# working.net
KiCad netlist of a schematic drawn in EAGLE
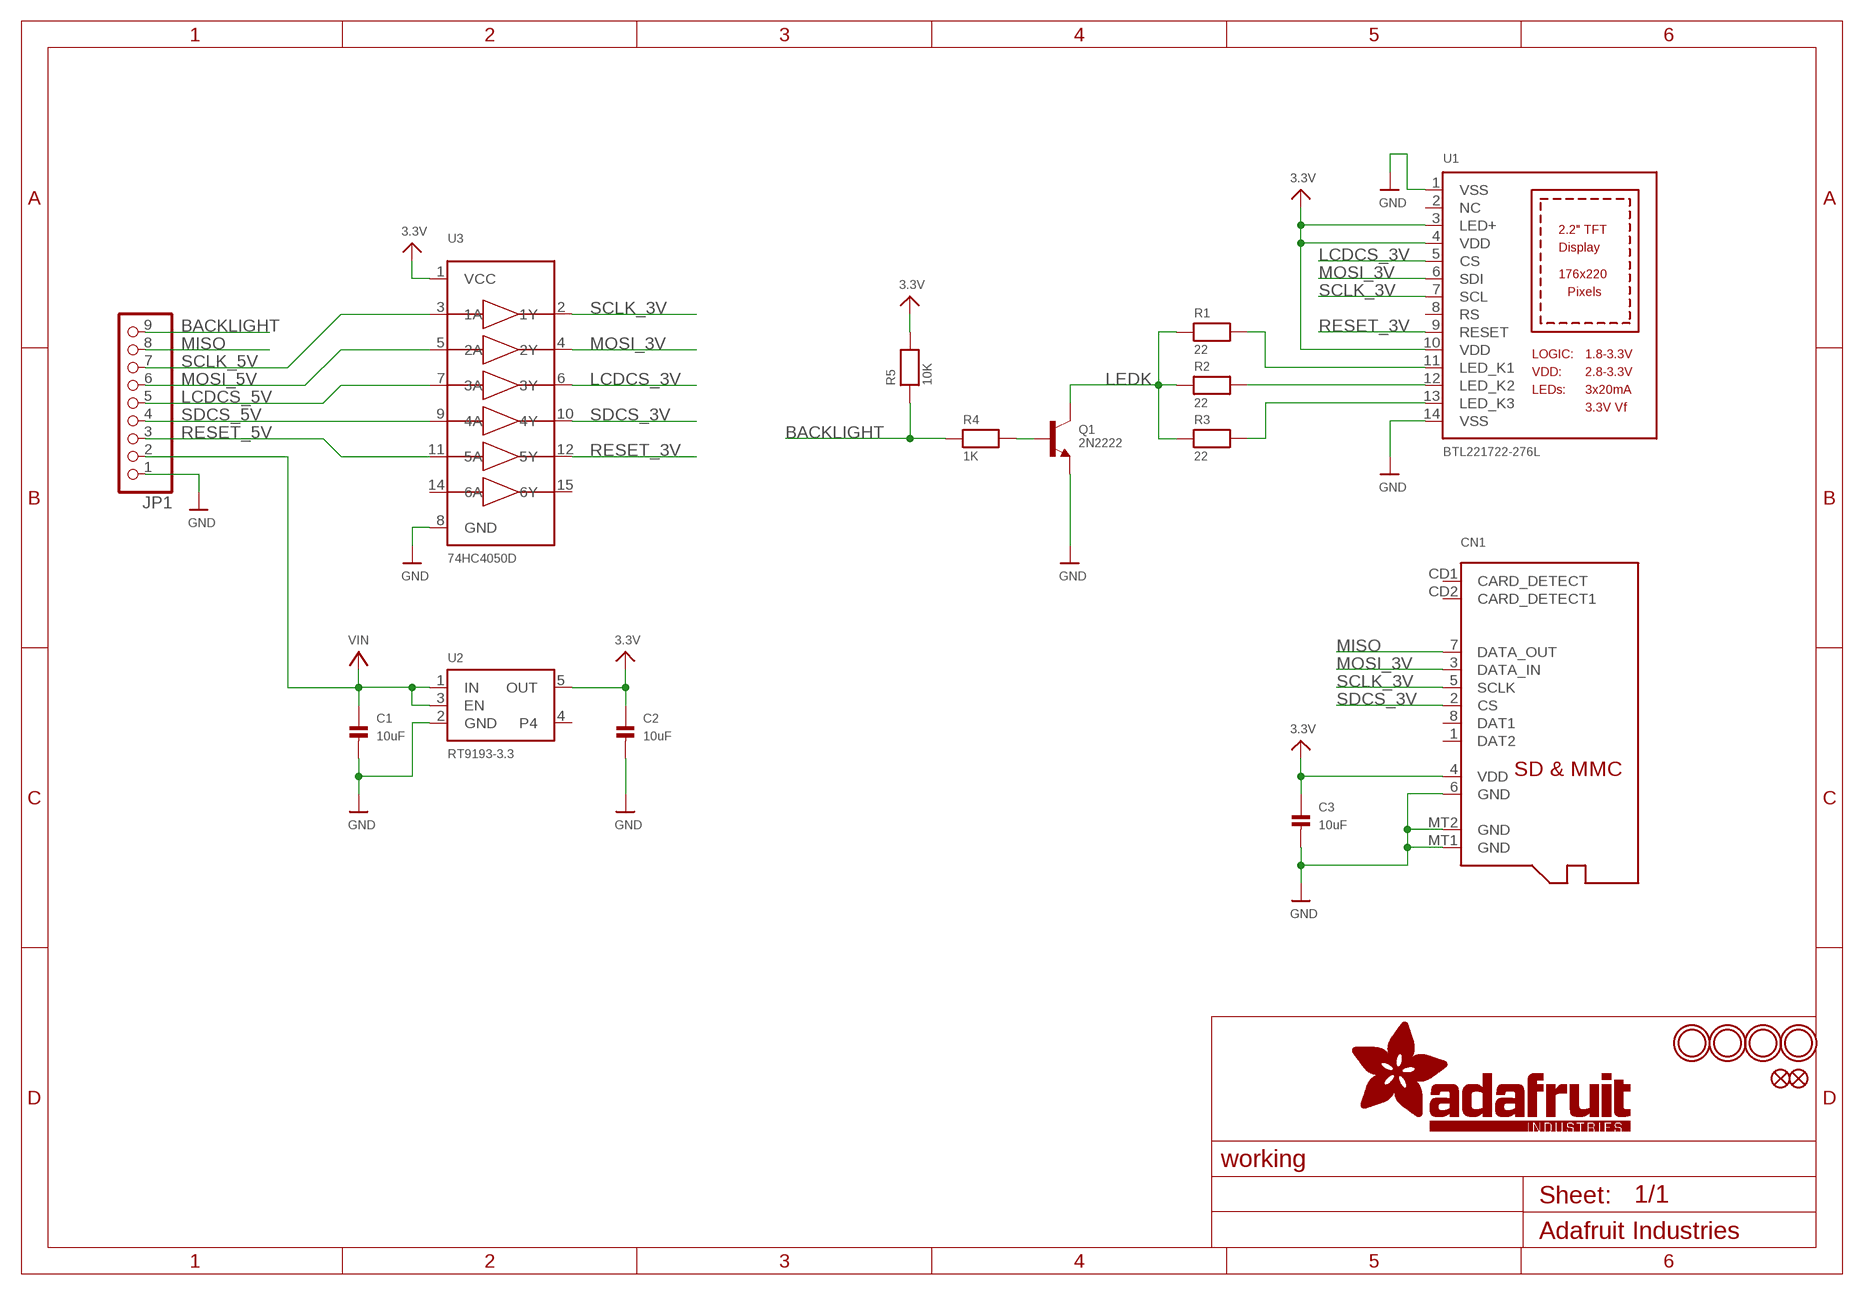
[diagram p0: schematic, sheet 1]

(export (version "E")
  (design (tool "Eeschema 10.0.6"))
  (components
    (comp (ref "C1")
      (value "10uF")
      (footprint "eagle-import:0805")
      (libsource (lib "eagle-import") (part "CAP_CERAMIC0805"))
    )
    (comp (ref "C2")
      (value "10uF")
      (footprint "eagle-import:0805")
      (libsource (lib "eagle-import") (part "CAP_CERAMIC0805"))
    )
    (comp (ref "C3")
      (value "10uF")
      (footprint "eagle-import:0805")
      (libsource (lib "eagle-import") (part "CAP_CERAMIC0805"))
    )
    (comp (ref "CN1")
      (value "MICROSD")
      (footprint "eagle-import:MICROSD")
      (libsource (lib "eagle-import") (part "MICROSD"))
    )
    (comp (ref "FID1")
      (value "FIDUCIAL\"\"")
      (footprint "eagle-import:FIDUCIAL_1MM")
      (libsource (lib "eagle-import") (part "FIDUCIAL{dblquote}{dblquote}"))
    )
    (comp (ref "FID2")
      (value "FIDUCIAL\"\"")
      (footprint "eagle-import:FIDUCIAL_1MM")
      (libsource (lib "eagle-import") (part "FIDUCIAL{dblquote}{dblquote}"))
    )
    (comp (ref "JP1")
      (value "HEADER-1X970MIL")
      (footprint "eagle-import:1X09_ROUND_70")
      (libsource (lib "eagle-import") (part "HEADER-1X970MIL"))
    )
    (comp (ref "Q1")
      (value "2N2222")
      (footprint "eagle-import:SOT23-WIDE")
      (libsource (lib "eagle-import") (part "TRANSISTOR_NPNWIDE"))
    )
    (comp (ref "R1")
      (value "22")
      (footprint "eagle-import:0805")
      (libsource (lib "eagle-import") (part "RESISTOR0805"))
    )
    (comp (ref "R2")
      (value "22")
      (footprint "eagle-import:0805")
      (libsource (lib "eagle-import") (part "RESISTOR0805"))
    )
    (comp (ref "R3")
      (value "22")
      (footprint "eagle-import:0805")
      (libsource (lib "eagle-import") (part "RESISTOR0805"))
    )
    (comp (ref "R4")
      (value "1K")
      (footprint "eagle-import:0805")
      (libsource (lib "eagle-import") (part "RESISTOR0805"))
    )
    (comp (ref "R5")
      (value "10K")
      (footprint "eagle-import:0805")
      (libsource (lib "eagle-import") (part "RESISTOR0805"))
    )
    (comp (ref "U$2")
      (value "MOUNTINGHOLE2.5")
      (footprint "eagle-import:MOUNTINGHOLE_2.5_PLATED")
      (libsource (lib "eagle-import") (part "MOUNTINGHOLE2.5"))
    )
    (comp (ref "U$3")
      (value "MOUNTINGHOLE2.5")
      (footprint "eagle-import:MOUNTINGHOLE_2.5_PLATED")
      (libsource (lib "eagle-import") (part "MOUNTINGHOLE2.5"))
    )
    (comp (ref "U$4")
      (value "MOUNTINGHOLE2.5")
      (footprint "eagle-import:MOUNTINGHOLE_2.5_PLATED")
      (libsource (lib "eagle-import") (part "MOUNTINGHOLE2.5"))
    )
    (comp (ref "U$5")
      (value "MOUNTINGHOLE2.5")
      (footprint "eagle-import:MOUNTINGHOLE_2.5_PLATED")
      (libsource (lib "eagle-import") (part "MOUNTINGHOLE2.5"))
    )
    (comp (ref "U1")
      (value "BTL221722-276L")
      (footprint "eagle-import:BTL221722-276L")
      (libsource (lib "eagle-import") (part "DISP_LCD_BTL221722-276L"))
    )
    (comp (ref "U2")
      (value "RT9193-3.3")
      (footprint "eagle-import:SOT23-5")
      (libsource (lib "eagle-import") (part "VREG_SOT23-5"))
    )
    (comp (ref "U3")
      (value "74HC4050D")
      (footprint "eagle-import:SOIC16")
      (libsource (lib "eagle-import") (part "74HC4050D"))
    )
  )
  (nets
    (net (code "1") (name "/BACKLIGHT") (class "Default")
      (node (ref "JP1") (pin "9") (pinfunction "9_9") (pintype "passive"))
      (node (ref "R4") (pin "1") (pinfunction "1_1") (pintype "passive"))
      (node (ref "R5") (pin "1") (pinfunction "1_1") (pintype "passive"))
    )
    (net (code "2") (name "/LCDCS_3V") (class "Default")
      (node (ref "U1") (pin "5") (pinfunction "CS_5") (pintype "bidirectional"))
      (node (ref "U3") (pin "6") (pinfunction "3Y_6") (pintype "bidirectional"))
    )
    (net (code "3") (name "/LCDCS_5V") (class "Default")
      (node (ref "JP1") (pin "5") (pinfunction "5_5") (pintype "passive"))
      (node (ref "U3") (pin "7") (pinfunction "3A_7") (pintype "bidirectional"))
    )
    (net (code "4") (name "/LEDK") (class "Default")
      (node (ref "Q1") (pin "3") (pinfunction "C_3") (pintype "passive"))
      (node (ref "R1") (pin "1") (pinfunction "1_1") (pintype "passive"))
      (node (ref "R2") (pin "1") (pinfunction "1_1") (pintype "passive"))
      (node (ref "R3") (pin "1") (pinfunction "1_1") (pintype "passive"))
    )
    (net (code "5") (name "/MISO") (class "Default")
      (node (ref "CN1") (pin "7") (pinfunction "DATA_OUT_7") (pintype "output"))
      (node (ref "JP1") (pin "8") (pinfunction "8_8") (pintype "passive"))
    )
    (net (code "6") (name "/MOSI_3V") (class "Default")
      (node (ref "CN1") (pin "3") (pinfunction "DATA_IN_3") (pintype "input"))
      (node (ref "U1") (pin "6") (pinfunction "SDI_6") (pintype "bidirectional"))
      (node (ref "U3") (pin "4") (pinfunction "2Y_4") (pintype "bidirectional"))
    )
    (net (code "7") (name "/MOSI_5V") (class "Default")
      (node (ref "JP1") (pin "6") (pinfunction "6_6") (pintype "passive"))
      (node (ref "U3") (pin "5") (pinfunction "2A_5") (pintype "bidirectional"))
    )
    (net (code "8") (name "/RESET_3V") (class "Default")
      (node (ref "U1") (pin "9") (pinfunction "RESET_9") (pintype "bidirectional"))
      (node (ref "U3") (pin "12") (pinfunction "5Y_12") (pintype "bidirectional"))
    )
    (net (code "9") (name "/RESET_5V") (class "Default")
      (node (ref "JP1") (pin "3") (pinfunction "3_3") (pintype "passive"))
      (node (ref "U3") (pin "11") (pinfunction "5A_11") (pintype "bidirectional"))
    )
    (net (code "10") (name "/SCLK_3V") (class "Default")
      (node (ref "CN1") (pin "5") (pinfunction "SCLK_5") (pintype "input"))
      (node (ref "U1") (pin "7") (pinfunction "SCL_7") (pintype "bidirectional"))
      (node (ref "U3") (pin "2") (pinfunction "1Y_2") (pintype "bidirectional"))
    )
    (net (code "11") (name "/SCLK_5V") (class "Default")
      (node (ref "JP1") (pin "7") (pinfunction "7_7") (pintype "passive"))
      (node (ref "U3") (pin "3") (pinfunction "1A_3") (pintype "bidirectional"))
    )
    (net (code "12") (name "/SDCS_3V") (class "Default")
      (node (ref "CN1") (pin "2") (pinfunction "CS_2") (pintype "input"))
      (node (ref "U3") (pin "10") (pinfunction "4Y_10") (pintype "bidirectional"))
    )
    (net (code "13") (name "/SDCS_5V") (class "Default")
      (node (ref "JP1") (pin "4") (pinfunction "4_4") (pintype "passive"))
      (node (ref "U3") (pin "9") (pinfunction "4A_9") (pintype "bidirectional"))
    )
    (net (code "14") (name "3.3V") (class "Default")
      (node (ref "C2") (pin "1") (pinfunction "P$1_1") (pintype "passive"))
      (node (ref "C3") (pin "1") (pinfunction "P$1_1") (pintype "passive"))
      (node (ref "CN1") (pin "4") (pinfunction "VDD_4") (pintype "power_in"))
      (node (ref "R5") (pin "2") (pinfunction "2_2") (pintype "passive"))
      (node (ref "U1") (pin "10") (pinfunction "VDD_10") (pintype "power_in"))
      (node (ref "U1") (pin "3") (pinfunction "LED+_3") (pintype "power_in"))
      (node (ref "U1") (pin "4") (pinfunction "VDD_4") (pintype "power_in"))
      (node (ref "U2") (pin "5") (pinfunction "OUT_5") (pintype "bidirectional"))
      (node (ref "U3") (pin "1") (pinfunction "VCC_1") (pintype "bidirectional"))
    )
    (net (code "15") (name "GND") (class "Default")
      (node (ref "C1") (pin "2") (pinfunction "P$2_2") (pintype "passive"))
      (node (ref "C2") (pin "2") (pinfunction "P$2_2") (pintype "passive"))
      (node (ref "C3") (pin "2") (pinfunction "P$2_2") (pintype "passive"))
      (node (ref "CN1") (pin "6") (pinfunction "GND_6") (pintype "power_in"))
      (node (ref "CN1") (pin "MT1") (pinfunction "GND_MT1") (pintype "power_in"))
      (node (ref "CN1") (pin "MT2") (pinfunction "GND_MT2") (pintype "power_in"))
      (node (ref "JP1") (pin "1") (pinfunction "1_1") (pintype "passive"))
      (node (ref "Q1") (pin "2") (pinfunction "E_2") (pintype "passive"))
      (node (ref "U1") (pin "1") (pinfunction "VSS_1") (pintype "power_in"))
      (node (ref "U1") (pin "14") (pinfunction "VSS_14") (pintype "power_in"))
      (node (ref "U2") (pin "2") (pinfunction "GND_2") (pintype "bidirectional"))
      (node (ref "U3") (pin "8") (pinfunction "GND_8") (pintype "bidirectional"))
    )
    (net (code "16") (name "Net-(Q1-B)") (class "Default")
      (node (ref "Q1") (pin "1") (pinfunction "B_1") (pintype "passive"))
      (node (ref "R4") (pin "2") (pinfunction "2_2") (pintype "passive"))
    )
    (net (code "17") (name "Net-(U1-LED_K1)") (class "Default")
      (node (ref "R1") (pin "2") (pinfunction "2_2") (pintype "passive"))
      (node (ref "U1") (pin "11") (pinfunction "LED_K1_11") (pintype "power_in"))
    )
    (net (code "18") (name "Net-(U1-LED_K2)") (class "Default")
      (node (ref "R2") (pin "2") (pinfunction "2_2") (pintype "passive"))
      (node (ref "U1") (pin "12") (pinfunction "LED_K2_12") (pintype "power_in"))
    )
    (net (code "19") (name "Net-(U1-LED_K3)") (class "Default")
      (node (ref "R3") (pin "2") (pinfunction "2_2") (pintype "passive"))
      (node (ref "U1") (pin "13") (pinfunction "LED_K3_13") (pintype "power_in"))
    )
    (net (code "20") (name "VIN") (class "Default")
      (node (ref "C1") (pin "1") (pinfunction "P$1_1") (pintype "passive"))
      (node (ref "JP1") (pin "2") (pinfunction "2_2") (pintype "passive"))
      (node (ref "U2") (pin "1") (pinfunction "IN_1") (pintype "bidirectional"))
      (node (ref "U2") (pin "3") (pinfunction "EN_3") (pintype "bidirectional"))
    )
    (net (code "21") (name "unconnected-(CN1-CARD_DETECT-PadCD1)") (class "Default")
      (node (ref "CN1") (pin "CD1") (pinfunction "CARD_DETECT_CD1") (pintype "passive"))
    )
    (net (code "22") (name "unconnected-(CN1-CARD_DETECT1-PadCD2)") (class "Default")
      (node (ref "CN1") (pin "CD2") (pinfunction "CARD_DETECT1_CD2") (pintype "passive"))
    )
    (net (code "23") (name "unconnected-(CN1-DAT1-Pad8)") (class "Default")
      (node (ref "CN1") (pin "8") (pinfunction "DAT1_8") (pintype "bidirectional"))
    )
    (net (code "24") (name "unconnected-(CN1-DAT2-Pad1)") (class "Default")
      (node (ref "CN1") (pin "1") (pinfunction "DAT2_1") (pintype "bidirectional"))
    )
    (net (code "25") (name "unconnected-(U1-NC-Pad2)") (class "Default")
      (node (ref "U1") (pin "2") (pinfunction "NC_2") (pintype "no_connect"))
    )
    (net (code "26") (name "unconnected-(U1-RS-Pad8)") (class "Default")
      (node (ref "U1") (pin "8") (pinfunction "RS_8") (pintype "bidirectional"))
    )
    (net (code "27") (name "unconnected-(U2-P4-Pad4)") (class "Default")
      (node (ref "U2") (pin "4") (pinfunction "P4_4") (pintype "bidirectional"))
    )
    (net (code "28") (name "unconnected-(U3-6A-Pad14)") (class "Default")
      (node (ref "U3") (pin "14") (pinfunction "6A_14") (pintype "bidirectional"))
    )
    (net (code "29") (name "unconnected-(U3-6Y-Pad15)") (class "Default")
      (node (ref "U3") (pin "15") (pinfunction "6Y_15") (pintype "bidirectional"))
    )
  )
)
